# OpenBook.net
KiCad netlist of a schematic drawn in EAGLE
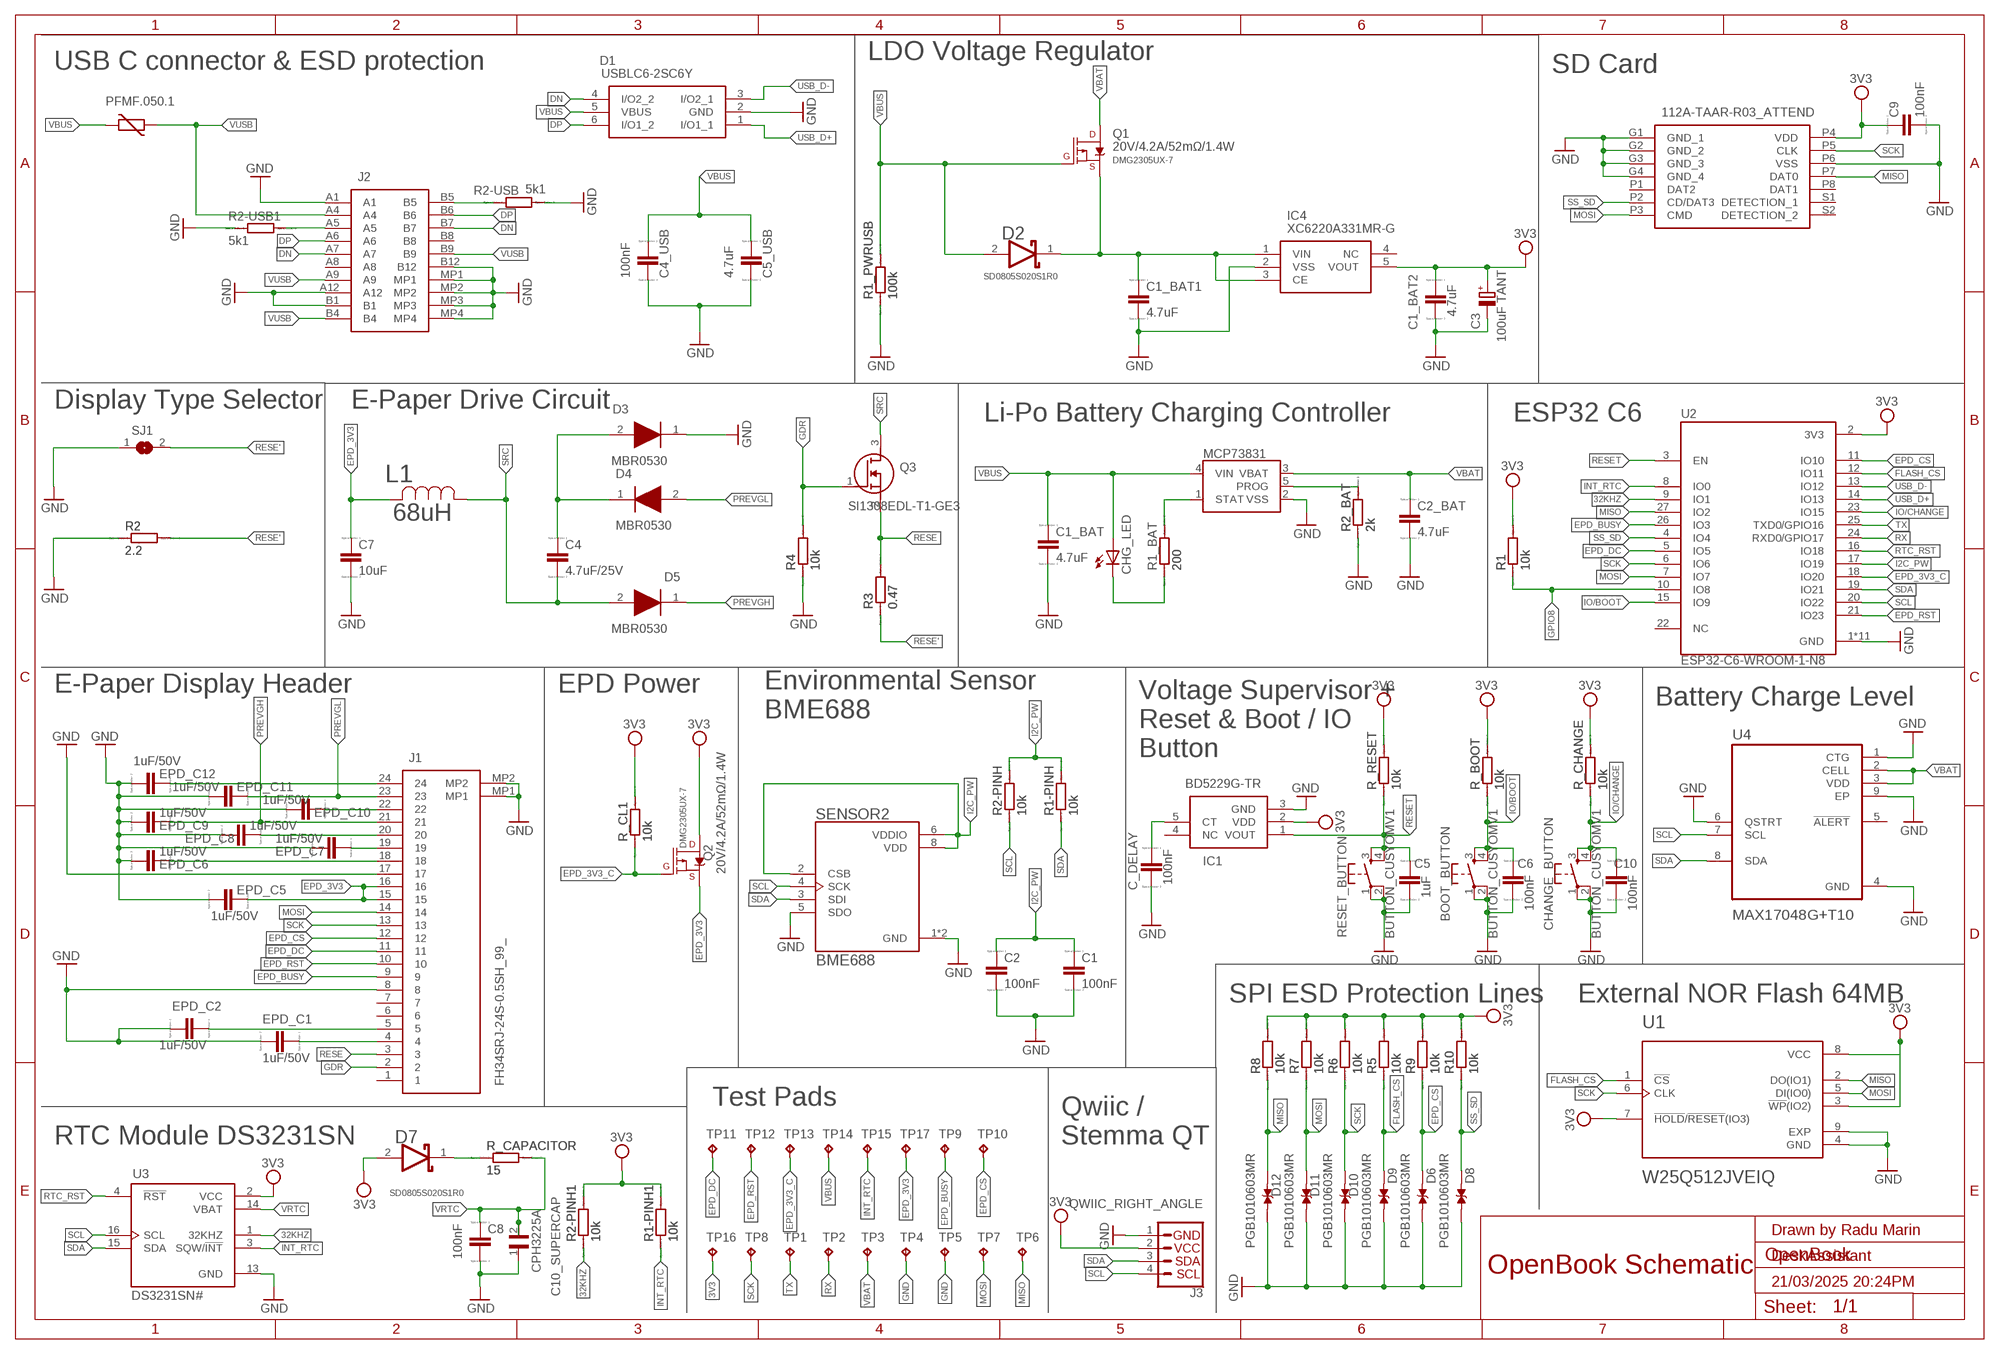
[diagram p0: schematic, sheet 1]

(export (version "E")
  (design (tool "Eeschema 10.0.6"))
  (components
    (comp (ref "BOOT_BUTTON")
      (value "BUTTON_CUSYOMV1")
      (footprint "eagle-import:MYBUTTON")
      (libsource (lib "eagle-import") (part "BUTTON_CUSYOMV1"))
    )
    (comp (ref "C1")
      (value "100nF")
      (footprint "eagle-import:EAGLE-LTSPICE_C0402")
      (libsource (lib "eagle-import") (part "EAGLE-LTSPICE_CC0402"))
    )
    (comp (ref "C1_BAT")
      (value "4.7uF")
      (footprint "eagle-import:EAGLE-LTSPICE_C0402")
      (libsource (lib "eagle-import") (part "EAGLE-LTSPICE_CC0402"))
    )
    (comp (ref "C1_BAT1")
      (value "4.7uF")
      (footprint "eagle-import:EAGLE-LTSPICE_C0402")
      (libsource (lib "eagle-import") (part "EAGLE-LTSPICE_CC0402"))
    )
    (comp (ref "C1_BAT2")
      (value "4.7uF")
      (footprint "eagle-import:EAGLE-LTSPICE_C0402")
      (libsource (lib "eagle-import") (part "EAGLE-LTSPICE_CC0402"))
    )
    (comp (ref "C2")
      (value "100nF")
      (footprint "eagle-import:EAGLE-LTSPICE_C0402")
      (libsource (lib "eagle-import") (part "EAGLE-LTSPICE_CC0402"))
    )
    (comp (ref "C2_BAT")
      (value "4.7uF")
      (footprint "eagle-import:EAGLE-LTSPICE_C0402")
      (libsource (lib "eagle-import") (part "EAGLE-LTSPICE_CC0402"))
    )
    (comp (ref "C3")
      (value "100uF TANT")
      (footprint "eagle-import:RCL_CT3528")
      (libsource (lib "eagle-import") (part "RCL_CPOL-EUCT3528"))
    )
    (comp (ref "C4")
      (value "4.7uF/25V")
      (footprint "eagle-import:EAGLE-LTSPICE_C0402")
      (libsource (lib "eagle-import") (part "EAGLE-LTSPICE_CC0402"))
    )
    (comp (ref "C4_USB")
      (value "100nF")
      (footprint "eagle-import:EAGLE-LTSPICE_C0402")
      (libsource (lib "eagle-import") (part "EAGLE-LTSPICE_CC0402"))
    )
    (comp (ref "C5")
      (value "1uF")
      (footprint "eagle-import:EAGLE-LTSPICE_C0402")
      (libsource (lib "eagle-import") (part "EAGLE-LTSPICE_CC0402"))
    )
    (comp (ref "C5_USB")
      (value "4.7uF")
      (footprint "eagle-import:EAGLE-LTSPICE_C0402")
      (libsource (lib "eagle-import") (part "EAGLE-LTSPICE_CC0402"))
    )
    (comp (ref "C6")
      (value "100nF")
      (footprint "eagle-import:EAGLE-LTSPICE_C0402")
      (libsource (lib "eagle-import") (part "EAGLE-LTSPICE_CC0402"))
    )
    (comp (ref "C7")
      (value "10uF")
      (footprint "eagle-import:EAGLE-LTSPICE_C0402")
      (libsource (lib "eagle-import") (part "EAGLE-LTSPICE_CC0402"))
    )
    (comp (ref "C8")
      (value "100nF")
      (footprint "eagle-import:EAGLE-LTSPICE_C0402")
      (libsource (lib "eagle-import") (part "EAGLE-LTSPICE_CC0402"))
    )
    (comp (ref "C9")
      (value "100nF")
      (footprint "eagle-import:EAGLE-LTSPICE_C0402")
      (libsource (lib "eagle-import") (part "EAGLE-LTSPICE_CC0402"))
    )
    (comp (ref "C10")
      (value "100nF")
      (footprint "eagle-import:EAGLE-LTSPICE_C0402")
      (libsource (lib "eagle-import") (part "EAGLE-LTSPICE_CC0402"))
    )
    (comp (ref "C10_SUPERCAP")
      (value "CPH3225A")
      (footprint "eagle-import:CAPCP3225X100N")
      (fields (field (name "MF") "Seiko Instruments"))
      (libsource (lib "eagle-import") (part "CPH3225A"))
    )
    (comp (ref "CHANGE_BUTTON")
      (value "BUTTON_CUSYOMV1")
      (footprint "eagle-import:MYBUTTON")
      (libsource (lib "eagle-import") (part "BUTTON_CUSYOMV1"))
    )
    (comp (ref "CHG_LED")
      (value "SMD-LED0603")
      (footprint "eagle-import:ADAFRUIT_CHIP-LED0603")
      (libsource (lib "eagle-import") (part "ADAFRUIT_LEDCHIP-LED0603"))
    )
    (comp (ref "C_DELAY")
      (value "100nF")
      (footprint "eagle-import:EAGLE-LTSPICE_C0402")
      (libsource (lib "eagle-import") (part "EAGLE-LTSPICE_CC0402"))
    )
    (comp (ref "D1")
      (value "USBLC6-2SC6Y")
      (footprint "eagle-import:SOT95P280X145-6N")
      (fields (field (name "MF") "STMicroelectronics"))
      (libsource (lib "eagle-import") (part "USBLC6-2SC6Y"))
    )
    (comp (ref "D2")
      (value "ESP32_WROVER_AVX---SD0805S020S1R0_AVX_SD0805S020S1R0_0_0AVX_SD0805S020S1R0_0_0")
      (footprint "eagle-import:ESP32_WROVER_AVX---SD0805S020S1R0_AVX_SD0805S020S1R0_0")
      (fields
        (field (name "DIGIKEY_PART_NUMBER") "478-7800-1-ND")
        (field (name "MF") "AVX")
        (field (name "MOUSER_PART_NUMBER") "581-SD0805S020S1R0")
      )
      (libsource (lib "eagle-import") (part "ESP32_WROVER_AVX---SD0805S020S1R0_AVX_SD0805S020S1R0_0_0AVX_SD0805S020S1R0_0_0"))
    )
    (comp (ref "D3")
      (value "MBR0530")
      (footprint "eagle-import:SOD3716X135N")
      (fields (field (name "MF") "ON Semiconductor"))
      (libsource (lib "eagle-import") (part "MBR0530"))
    )
    (comp (ref "D4")
      (value "MBR0530")
      (footprint "eagle-import:SOD3716X135N")
      (fields (field (name "MF") "ON Semiconductor"))
      (libsource (lib "eagle-import") (part "MBR0530"))
    )
    (comp (ref "D5")
      (value "MBR0530")
      (footprint "eagle-import:SOD3716X135N")
      (fields (field (name "MF") "ON Semiconductor"))
      (libsource (lib "eagle-import") (part "MBR0530"))
    )
    (comp (ref "D6")
      (value "PGB1010603MR")
      (footprint "eagle-import:DIOC1608X36N")
      (fields (field (name "MF") "Littelfuse Inc."))
      (libsource (lib "eagle-import") (part "PGB1010603MR"))
    )
    (comp (ref "D7")
      (value "ESP32_WROVER_AVX---SD0805S020S1R0_AVX_SD0805S020S1R0_0_0AVX_SD0805S020S1R0_0_0")
      (footprint "eagle-import:ESP32_WROVER_AVX---SD0805S020S1R0_AVX_SD0805S020S1R0_0")
      (fields
        (field (name "DIGIKEY_PART_NUMBER") "478-7800-1-ND")
        (field (name "MF") "AVX")
        (field (name "MOUSER_PART_NUMBER") "581-SD0805S020S1R0")
      )
      (libsource (lib "eagle-import") (part "ESP32_WROVER_AVX---SD0805S020S1R0_AVX_SD0805S020S1R0_0_0AVX_SD0805S020S1R0_0_0"))
    )
    (comp (ref "D8")
      (value "PGB1010603MR")
      (footprint "eagle-import:DIOC1608X36N")
      (fields (field (name "MF") "Littelfuse Inc."))
      (libsource (lib "eagle-import") (part "PGB1010603MR"))
    )
    (comp (ref "D9")
      (value "PGB1010603MR")
      (footprint "eagle-import:DIOC1608X36N")
      (fields (field (name "MF") "Littelfuse Inc."))
      (libsource (lib "eagle-import") (part "PGB1010603MR"))
    )
    (comp (ref "D10")
      (value "PGB1010603MR")
      (footprint "eagle-import:DIOC1608X36N")
      (fields (field (name "MF") "Littelfuse Inc."))
      (libsource (lib "eagle-import") (part "PGB1010603MR"))
    )
    (comp (ref "D11")
      (value "PGB1010603MR")
      (footprint "eagle-import:DIOC1608X36N")
      (fields (field (name "MF") "Littelfuse Inc."))
      (libsource (lib "eagle-import") (part "PGB1010603MR"))
    )
    (comp (ref "D12")
      (value "PGB1010603MR")
      (footprint "eagle-import:DIOC1608X36N")
      (fields (field (name "MF") "Littelfuse Inc."))
      (libsource (lib "eagle-import") (part "PGB1010603MR"))
    )
    (comp (ref "EPD_C1")
      (value "1uF/50V")
      (footprint "eagle-import:EAGLE-LTSPICE_C0402")
      (libsource (lib "eagle-import") (part "EAGLE-LTSPICE_CC0402"))
    )
    (comp (ref "EPD_C2")
      (value "1uF/50V")
      (footprint "eagle-import:EAGLE-LTSPICE_C0402")
      (libsource (lib "eagle-import") (part "EAGLE-LTSPICE_CC0402"))
    )
    (comp (ref "EPD_C5")
      (value "1uF/50V")
      (footprint "eagle-import:EAGLE-LTSPICE_C0402")
      (libsource (lib "eagle-import") (part "EAGLE-LTSPICE_CC0402"))
    )
    (comp (ref "EPD_C6")
      (value "1uF/50V")
      (footprint "eagle-import:EAGLE-LTSPICE_C0402")
      (libsource (lib "eagle-import") (part "EAGLE-LTSPICE_CC0402"))
    )
    (comp (ref "EPD_C7")
      (value "1uF/50V")
      (footprint "eagle-import:EAGLE-LTSPICE_C0402")
      (libsource (lib "eagle-import") (part "EAGLE-LTSPICE_CC0402"))
    )
    (comp (ref "EPD_C8")
      (value "1uF/50V")
      (footprint "eagle-import:EAGLE-LTSPICE_C0402")
      (libsource (lib "eagle-import") (part "EAGLE-LTSPICE_CC0402"))
    )
    (comp (ref "EPD_C9")
      (value "1uF/50V")
      (footprint "eagle-import:EAGLE-LTSPICE_C0402")
      (libsource (lib "eagle-import") (part "EAGLE-LTSPICE_CC0402"))
    )
    (comp (ref "EPD_C10")
      (value "1uF/50V")
      (footprint "eagle-import:EAGLE-LTSPICE_C0402")
      (libsource (lib "eagle-import") (part "EAGLE-LTSPICE_CC0402"))
    )
    (comp (ref "EPD_C11")
      (value "1uF/50V")
      (footprint "eagle-import:EAGLE-LTSPICE_C0402")
      (libsource (lib "eagle-import") (part "EAGLE-LTSPICE_CC0402"))
    )
    (comp (ref "EPD_C12")
      (value "1uF/50V")
      (footprint "eagle-import:EAGLE-LTSPICE_C0402")
      (libsource (lib "eagle-import") (part "EAGLE-LTSPICE_CC0402"))
    )
    (comp (ref "IC1")
      (value "BD5229G-TR")
      (footprint "eagle-import:SOT95P280X125-5N")
      (fields (field (name "MOUSER_PART_NUMBER") "755-BD5229G-TR"))
      (libsource (lib "eagle-import") (part "BD5229G-TR"))
    )
    (comp (ref "IC4")
      (value "XC6220A331MR-G")
      (footprint "eagle-import:SOT95P280X120-5N")
      (fields (field (name "MOUSER_PART_NUMBER") "865-XC6220A331MR-G"))
      (libsource (lib "eagle-import") (part "XC6220A331MR-G"))
    )
    (comp (ref "J1")
      (value "FH34SRJ-24S-0.5SH_99_")
      (footprint "eagle-import:FH34SRJ24S05SH99")
      (fields
        (field (name "MANUFACTURER_PART_NUMBER") "FH34SRJ-24S-0.5SH(99)")
        (field (name "MOUSER_PART_NUMBER") "798-FH34SRJ24S05SH99")
      )
      (libsource (lib "eagle-import") (part "FH34SRJ-24S-0.5SH_99_"))
    )
    (comp (ref "J2")
      (value "SAMACSYS_PARTS_USB4110-GF-A")
      (footprint "eagle-import:SAMACSYS_PARTS_USB4110GFA")
      (fields
        (field (name "MANUFACTURER_PART_NUMBER") "USB4110-GF-A")
        (field (name "MOUSER_PART_NUMBER") "640-USB4110-GF-A")
      )
      (libsource (lib "eagle-import") (part "SAMACSYS_PARTS_USB4110-GF-A"))
    )
    (comp (ref "J3")
      (value "QWIIC_RIGHT_ANGLE")
      (footprint "eagle-import:JST04_1MM_RA")
      (libsource (lib "eagle-import") (part "QWIIC_CONNECTORJS-1MM"))
    )
    (comp (ref "J10")
      (value "112A-TAAR-R03_ATTEND")
      (footprint "eagle-import:112ATAARR03ATTEND")
      (fields (field (name "MANUFACTURER_PART_NUMBER") "112A-TAAR-R03 ATTEND"))
      (libsource (lib "eagle-import") (part "112A-TAAR-R03_ATTEND"))
    )
    (comp (ref "L1")
      (value "68uH")
      (footprint "eagle-import:IND_4828-WE-TPC_WRE")
      (fields
        (field (name "MANUFACTURER_PART_NUMBER") "744043680")
        (field (name "COPYRIGHT") "Copyright (C) 2024 Ultra Librarian. All rights reserved.")
      )
      (libsource (lib "eagle-import") (part "744043680IND_4828-WE-TPC_WRE"))
    )
    (comp (ref "MCP73831")
      (value "ESP32_WROVER_SPARKFUN-IC-POWER_MCP73831")
      (footprint "eagle-import:ESP32_WROVER_SPARKFUN-IC-POWER_SOT23-5")
      (libsource (lib "eagle-import") (part "ESP32_WROVER_SPARKFUN-IC-POWER_MCP73831"))
    )
    (comp (ref "PFMF.050.1")
      (value "ESP32C6_VARISTORCN1812")
      (footprint "eagle-import:ESP32C6_VARISTOR_CT_CN1812")
      (libsource (lib "eagle-import") (part "ESP32C6_VARISTORCN1812"))
    )
    (comp (ref "Q1")
      (value "20V/4.2A/52mΩ/1.4W")
      (footprint "eagle-import:ESP32_WROVER_SPARKFUN-DISCRETESEMI_SOT23-3")
      (libsource (lib "eagle-import") (part "ESP32_WROVER_SPARKFUN-DISCRETESEMI_MOSFET_PCH-DMG2305UX-7"))
    )
    (comp (ref "Q2")
      (value "20V/4.2A/52mΩ/1.4W")
      (footprint "eagle-import:ESP32_WROVER_SPARKFUN-DISCRETESEMI_SOT23-3")
      (libsource (lib "eagle-import") (part "ESP32_WROVER_SPARKFUN-DISCRETESEMI_MOSFET_PCH-DMG2305UX-7"))
    )
    (comp (ref "Q3")
      (value "SI1308EDL-T1-GE3")
      (footprint "eagle-import:SOT65P210X110-3N")
      (fields (field (name "MF") "Vishay Siliconix"))
      (libsource (lib "eagle-import") (part "SI1308EDL-T1-GE3"))
    )
    (comp (ref "R1")
      (value "10k")
      (footprint "eagle-import:ESP32_WROVER_EAGLE-LTSPICE_R0402")
      (libsource (lib "eagle-import") (part "ESP32_WROVER_EAGLE-LTSPICE_RR0402"))
    )
    (comp (ref "R1-PINH")
      (value "10k")
      (footprint "eagle-import:ESP32_WROVER_EAGLE-LTSPICE_R0402")
      (libsource (lib "eagle-import") (part "ESP32_WROVER_EAGLE-LTSPICE_RR0402"))
    )
    (comp (ref "R1-PINH1")
      (value "10k")
      (footprint "eagle-import:ESP32_WROVER_EAGLE-LTSPICE_R0402")
      (libsource (lib "eagle-import") (part "ESP32_WROVER_EAGLE-LTSPICE_RR0402"))
    )
    (comp (ref "R1_BAT")
      (value "200")
      (footprint "eagle-import:ESP32_WROVER_EAGLE-LTSPICE_R0402")
      (libsource (lib "eagle-import") (part "ESP32_WROVER_EAGLE-LTSPICE_RR0402"))
    )
    (comp (ref "R1_PWRUSB")
      (value "100k")
      (footprint "eagle-import:ESP32_WROVER_EAGLE-LTSPICE_R0402")
      (libsource (lib "eagle-import") (part "ESP32_WROVER_EAGLE-LTSPICE_RR0402"))
    )
    (comp (ref "R2")
      (value "2.2")
      (footprint "eagle-import:ESP32_WROVER_EAGLE-LTSPICE_R0402")
      (libsource (lib "eagle-import") (part "ESP32_WROVER_EAGLE-LTSPICE_RR0402"))
    )
    (comp (ref "R2-PINH")
      (value "10k")
      (footprint "eagle-import:ESP32_WROVER_EAGLE-LTSPICE_R0402")
      (libsource (lib "eagle-import") (part "ESP32_WROVER_EAGLE-LTSPICE_RR0402"))
    )
    (comp (ref "R2-PINH1")
      (value "10k")
      (footprint "eagle-import:ESP32_WROVER_EAGLE-LTSPICE_R0402")
      (libsource (lib "eagle-import") (part "ESP32_WROVER_EAGLE-LTSPICE_RR0402"))
    )
    (comp (ref "R2-USB")
      (value "5k1")
      (footprint "eagle-import:ESP32_WROVER_EAGLE-LTSPICE_R0402")
      (libsource (lib "eagle-import") (part "ESP32_WROVER_EAGLE-LTSPICE_RR0402"))
    )
    (comp (ref "R2-USB1")
      (value "5k1")
      (footprint "eagle-import:ESP32_WROVER_EAGLE-LTSPICE_R0402")
      (libsource (lib "eagle-import") (part "ESP32_WROVER_EAGLE-LTSPICE_RR0402"))
    )
    (comp (ref "R2_BAT")
      (value "2k")
      (footprint "eagle-import:ESP32_WROVER_EAGLE-LTSPICE_R0402")
      (libsource (lib "eagle-import") (part "ESP32_WROVER_EAGLE-LTSPICE_RR0402"))
    )
    (comp (ref "R3")
      (value "0.47")
      (footprint "eagle-import:ESP32_WROVER_EAGLE-LTSPICE_R0402")
      (libsource (lib "eagle-import") (part "ESP32_WROVER_EAGLE-LTSPICE_RR0402"))
    )
    (comp (ref "R4")
      (value "10k")
      (footprint "eagle-import:ESP32_WROVER_EAGLE-LTSPICE_R0402")
      (libsource (lib "eagle-import") (part "ESP32_WROVER_EAGLE-LTSPICE_RR0402"))
    )
    (comp (ref "R5")
      (value "10k")
      (footprint "eagle-import:ESP32_WROVER_EAGLE-LTSPICE_R0402")
      (libsource (lib "eagle-import") (part "ESP32_WROVER_EAGLE-LTSPICE_RR0402"))
    )
    (comp (ref "R6")
      (value "10k")
      (footprint "eagle-import:ESP32_WROVER_EAGLE-LTSPICE_R0402")
      (libsource (lib "eagle-import") (part "ESP32_WROVER_EAGLE-LTSPICE_RR0402"))
    )
    (comp (ref "R7")
      (value "10k")
      (footprint "eagle-import:ESP32_WROVER_EAGLE-LTSPICE_R0402")
      (libsource (lib "eagle-import") (part "ESP32_WROVER_EAGLE-LTSPICE_RR0402"))
    )
    (comp (ref "R8")
      (value "10k")
      (footprint "eagle-import:ESP32_WROVER_EAGLE-LTSPICE_R0402")
      (libsource (lib "eagle-import") (part "ESP32_WROVER_EAGLE-LTSPICE_RR0402"))
    )
    (comp (ref "R9")
      (value "10k")
      (footprint "eagle-import:ESP32_WROVER_EAGLE-LTSPICE_R0402")
      (libsource (lib "eagle-import") (part "ESP32_WROVER_EAGLE-LTSPICE_RR0402"))
    )
    (comp (ref "R10")
      (value "10k")
      (footprint "eagle-import:ESP32_WROVER_EAGLE-LTSPICE_R0402")
      (libsource (lib "eagle-import") (part "ESP32_WROVER_EAGLE-LTSPICE_RR0402"))
    )
    (comp (ref "RESET_BUTTON")
      (value "BUTTON_CUSYOMV1")
      (footprint "eagle-import:MYBUTTON")
      (libsource (lib "eagle-import") (part "BUTTON_CUSYOMV1"))
    )
    (comp (ref "R_BOOT")
      (value "10k")
      (footprint "eagle-import:ESP32_WROVER_EAGLE-LTSPICE_R0402")
      (libsource (lib "eagle-import") (part "ESP32_WROVER_EAGLE-LTSPICE_RR0402"))
    )
    (comp (ref "R_CAPACITOR")
      (value "15")
      (footprint "eagle-import:ESP32_WROVER_EAGLE-LTSPICE_R0402")
      (libsource (lib "eagle-import") (part "ESP32_WROVER_EAGLE-LTSPICE_RR0402"))
    )
    (comp (ref "R_CHANGE")
      (value "10k")
      (footprint "eagle-import:ESP32_WROVER_EAGLE-LTSPICE_R0402")
      (libsource (lib "eagle-import") (part "ESP32_WROVER_EAGLE-LTSPICE_RR0402"))
    )
    (comp (ref "R_CL1")
      (value "10k")
      (footprint "eagle-import:ESP32_WROVER_EAGLE-LTSPICE_R0402")
      (libsource (lib "eagle-import") (part "ESP32_WROVER_EAGLE-LTSPICE_RR0402"))
    )
    (comp (ref "R_RESET")
      (value "10k")
      (footprint "eagle-import:ESP32_WROVER_EAGLE-LTSPICE_R0402")
      (libsource (lib "eagle-import") (part "ESP32_WROVER_EAGLE-LTSPICE_RR0402"))
    )
    (comp (ref "SENSOR2")
      (value "BME688")
      (footprint "eagle-import:ESP32_WROVER_BME680_PSON80P300X300X100-8N")
      (fields (field (name "MF") "Bosch Sensortec") (field (name "MP") "BME680"))
      (libsource (lib "eagle-import") (part "ESP32_WROVER_BME680_BME680"))
    )
    (comp (ref "SJ1") (value "1m") (footprint "eagle-import:SJ") (libsource (lib "eagle-import") (part "SJ")))
    (comp (ref "TP1")
      (value "TPTP20R")
      (footprint "eagle-import:TP20R")
      (libsource (lib "eagle-import") (part "TPTP20R"))
    )
    (comp (ref "TP2")
      (value "TPTP20R")
      (footprint "eagle-import:TP20R")
      (libsource (lib "eagle-import") (part "TPTP20R"))
    )
    (comp (ref "TP3")
      (value "TPTP20R")
      (footprint "eagle-import:TP20R")
      (libsource (lib "eagle-import") (part "TPTP20R"))
    )
    (comp (ref "TP4")
      (value "TPTP20R")
      (footprint "eagle-import:TP20R")
      (libsource (lib "eagle-import") (part "TPTP20R"))
    )
    (comp (ref "TP5")
      (value "TPTP20R")
      (footprint "eagle-import:TP20R")
      (libsource (lib "eagle-import") (part "TPTP20R"))
    )
    (comp (ref "TP6")
      (value "TPTP20R")
      (footprint "eagle-import:TP20R")
      (libsource (lib "eagle-import") (part "TPTP20R"))
    )
    (comp (ref "TP7")
      (value "TPTP20R")
      (footprint "eagle-import:TP20R")
      (libsource (lib "eagle-import") (part "TPTP20R"))
    )
    (comp (ref "TP8")
      (value "TPTP20R")
      (footprint "eagle-import:TP20R")
      (libsource (lib "eagle-import") (part "TPTP20R"))
    )
    (comp (ref "TP9")
      (value "TPTP20R")
      (footprint "eagle-import:TP20R")
      (libsource (lib "eagle-import") (part "TPTP20R"))
    )
    (comp (ref "TP10")
      (value "TPTP20R")
      (footprint "eagle-import:TP20R")
      (libsource (lib "eagle-import") (part "TPTP20R"))
    )
    (comp (ref "TP11")
      (value "TPTP20R")
      (footprint "eagle-import:TP20R")
      (libsource (lib "eagle-import") (part "TPTP20R"))
    )
    (comp (ref "TP12")
      (value "TPTP20R")
      (footprint "eagle-import:TP20R")
      (libsource (lib "eagle-import") (part "TPTP20R"))
    )
    (comp (ref "TP13")
      (value "TPTP20R")
      (footprint "eagle-import:TP20R")
      (libsource (lib "eagle-import") (part "TPTP20R"))
    )
    (comp (ref "TP14")
      (value "TPTP20R")
      (footprint "eagle-import:TP20R")
      (libsource (lib "eagle-import") (part "TPTP20R"))
    )
    (comp (ref "TP15")
      (value "TPTP20R")
      (footprint "eagle-import:TP20R")
      (libsource (lib "eagle-import") (part "TPTP20R"))
    )
    (comp (ref "TP16")
      (value "TPTP20R")
      (footprint "eagle-import:TP20R")
      (libsource (lib "eagle-import") (part "TPTP20R"))
    )
    (comp (ref "TP17")
      (value "TPTP20R")
      (footprint "eagle-import:TP20R")
      (libsource (lib "eagle-import") (part "TPTP20R"))
    )
    (comp (ref "U1")
      (value "W25Q512JVEIQ")
      (footprint "eagle-import:SON127P600X800X80-9N")
      (fields (field (name "MF") "Winbond Electronics"))
      (libsource (lib "eagle-import") (part "W25Q512JVEIQ"))
    )
    (comp (ref "U2")
      (value "ESP32-C6-WROOM-1-N8")
      (footprint "eagle-import:XCVR_ESP32-C6-WROOM-1-N8")
      (fields (field (name "MF") "Espressif Systems"))
      (libsource (lib "eagle-import") (part "ESP32-C6-WROOM-1-N8"))
    )
    (comp (ref "U3")
      (value "DS3231SN#")
      (footprint "eagle-import:SOIC127P1032X265-16N")
      (fields (field (name "MF") "Analog Devices"))
      (libsource (lib "eagle-import") (part "DS3231SN#"))
    )
    (comp (ref "U4")
      (value "MAX17048G+T10")
      (footprint "eagle-import:SON50P200X200X80-9N")
      (fields (field (name "MF") "Analog Devices"))
      (libsource (lib "eagle-import") (part "MAX17048G+T10"))
    )
  )
  (nets
    (net (code "1") (name "3V3") (class "Default")
      (node (ref "C1_BAT2") (pin "1") (pinfunction "1_1") (pintype "passive"))
      (node (ref "C3") (pin "+") (pinfunction "+_+") (pintype "passive"))
      (node (ref "C9") (pin "1") (pinfunction "1_1") (pintype "passive"))
      (node (ref "D7") (pin "2") (pinfunction "ANODE_2") (pintype "bidirectional"))
      (node (ref "IC1") (pin "2") (pinfunction "VDD_2") (pintype "bidirectional"))
      (node (ref "IC4") (pin "5") (pinfunction "VOUT_5") (pintype "bidirectional"))
      (node (ref "J10") (pin "P4") (pinfunction "VDD_P4") (pintype "bidirectional"))
      (node (ref "J3") (pin "2") (pinfunction "2_2") (pintype "power_in"))
      (node (ref "Q2") (pin "3") (pinfunction "D_3") (pintype "bidirectional"))
      (node (ref "R1") (pin "2") (pinfunction "2_2") (pintype "passive"))
      (node (ref "R1-PINH1") (pin "2") (pinfunction "2_2") (pintype "passive"))
      (node (ref "R10") (pin "2") (pinfunction "2_2") (pintype "passive"))
      (node (ref "R2-PINH1") (pin "2") (pinfunction "2_2") (pintype "passive"))
      (node (ref "R5") (pin "2") (pinfunction "2_2") (pintype "passive"))
      (node (ref "R6") (pin "2") (pinfunction "2_2") (pintype "passive"))
      (node (ref "R7") (pin "2") (pinfunction "2_2") (pintype "passive"))
      (node (ref "R8") (pin "2") (pinfunction "2_2") (pintype "passive"))
      (node (ref "R9") (pin "2") (pinfunction "2_2") (pintype "passive"))
      (node (ref "R_BOOT") (pin "2") (pinfunction "2_2") (pintype "passive"))
      (node (ref "R_CHANGE") (pin "2") (pinfunction "2_2") (pintype "passive"))
      (node (ref "R_CL1") (pin "2") (pinfunction "2_2") (pintype "passive"))
      (node (ref "R_RESET") (pin "2") (pinfunction "2_2") (pintype "passive"))
      (node (ref "TP16") (pin "TP") (pinfunction "TP_TP") (pintype "input"))
      (node (ref "U1") (pin "3") (pinfunction "~{WP}(IO2)_3") (pintype "bidirectional"))
      (node (ref "U1") (pin "7") (pinfunction "~{HOLD}/~{RESET}(IO3)_7") (pintype "bidirectional"))
      (node (ref "U1") (pin "8") (pinfunction "VCC_8") (pintype "power_in"))
      (node (ref "U2") (pin "2") (pinfunction "3V3_2") (pintype "power_in"))
      (node (ref "U3") (pin "2") (pinfunction "VCC_2") (pintype "power_in"))
    )
    (net (code "2") (name "32KHZ") (class "Default")
      (node (ref "R2-PINH1") (pin "1") (pinfunction "1_1") (pintype "passive"))
      (node (ref "U2") (pin "9") (pinfunction "IO1_9") (pintype "bidirectional"))
      (node (ref "U3") (pin "1") (pinfunction "32KHZ_1") (pintype "output"))
    )
    (net (code "3") (name "DN") (class "Default")
      (node (ref "D1") (pin "4") (pinfunction "I/O2_2_4") (pintype "bidirectional"))
      (node (ref "J2") (pin "A7") (pinfunction "A7_A7") (pintype "bidirectional"))
      (node (ref "J2") (pin "B7") (pinfunction "B7_B7") (pintype "bidirectional"))
    )
    (net (code "4") (name "DP") (class "Default")
      (node (ref "D1") (pin "6") (pinfunction "I/O1_2_6") (pintype "bidirectional"))
      (node (ref "J2") (pin "A6") (pinfunction "A6_A6") (pintype "bidirectional"))
      (node (ref "J2") (pin "B6") (pinfunction "B6_B6") (pintype "bidirectional"))
    )
    (net (code "5") (name "EPD_3V3") (class "Default")
      (node (ref "C7") (pin "1") (pinfunction "1_1") (pintype "passive"))
      (node (ref "EPD_C5") (pin "1") (pinfunction "1_1") (pintype "passive"))
      (node (ref "J1") (pin "15") (pinfunction "15_15") (pintype "bidirectional"))
      (node (ref "J1") (pin "16") (pinfunction "16_16") (pintype "bidirectional"))
      (node (ref "L1") (pin "2") (pinfunction "2_2") (pintype "passive"))
      (node (ref "Q2") (pin "2") (pinfunction "S_2") (pintype "bidirectional"))
      (node (ref "TP17") (pin "TP") (pinfunction "TP_TP") (pintype "input"))
    )
    (net (code "6") (name "EPD_3V3_C") (class "Default")
      (node (ref "Q2") (pin "1") (pinfunction "G_1") (pintype "bidirectional"))
      (node (ref "R_CL1") (pin "1") (pinfunction "1_1") (pintype "passive"))
      (node (ref "TP13") (pin "TP") (pinfunction "TP_TP") (pintype "input"))
      (node (ref "U2") (pin "18") (pinfunction "IO20_18") (pintype "bidirectional"))
    )
    (net (code "7") (name "EPD_BUSY") (class "Default")
      (node (ref "J1") (pin "9") (pinfunction "9_9") (pintype "bidirectional"))
      (node (ref "TP9") (pin "TP") (pinfunction "TP_TP") (pintype "input"))
      (node (ref "U2") (pin "26") (pinfunction "IO3_26") (pintype "bidirectional"))
    )
    (net (code "8") (name "EPD_CS") (class "Default")
      (node (ref "D6") (pin "2") (pinfunction "2_2") (pintype "passive"))
      (node (ref "J1") (pin "12") (pinfunction "12_12") (pintype "bidirectional"))
      (node (ref "R9") (pin "1") (pinfunction "1_1") (pintype "passive"))
      (node (ref "TP10") (pin "TP") (pinfunction "TP_TP") (pintype "input"))
      (node (ref "U2") (pin "11") (pinfunction "IO10_11") (pintype "bidirectional"))
    )
    (net (code "9") (name "EPD_DC") (class "Default")
      (node (ref "J1") (pin "11") (pinfunction "11_11") (pintype "bidirectional"))
      (node (ref "TP11") (pin "TP") (pinfunction "TP_TP") (pintype "input"))
      (node (ref "U2") (pin "5") (pinfunction "IO5_5") (pintype "bidirectional"))
    )
    (net (code "10") (name "EPD_RST") (class "Default")
      (node (ref "J1") (pin "10") (pinfunction "10_10") (pintype "bidirectional"))
      (node (ref "TP12") (pin "TP") (pinfunction "TP_TP") (pintype "input"))
      (node (ref "U2") (pin "21") (pinfunction "IO23_21") (pintype "bidirectional"))
    )
    (net (code "11") (name "FLASH_CS") (class "Default")
      (node (ref "D9") (pin "2") (pinfunction "2_2") (pintype "passive"))
      (node (ref "R5") (pin "1") (pinfunction "1_1") (pintype "passive"))
      (node (ref "U1") (pin "1") (pinfunction "~{CS}_1") (pintype "input"))
      (node (ref "U2") (pin "12") (pinfunction "IO11_12") (pintype "bidirectional"))
    )
    (net (code "12") (name "GDR") (class "Default")
      (node (ref "J1") (pin "2") (pinfunction "2_2") (pintype "bidirectional"))
      (node (ref "Q3") (pin "1") (pinfunction "G_1") (pintype "bidirectional"))
      (node (ref "R4") (pin "2") (pinfunction "2_2") (pintype "passive"))
    )
    (net (code "13") (name "GND") (class "Default")
      (node (ref "BOOT_BUTTON") (pin "1") (pinfunction "1_1") (pintype "passive"))
      (node (ref "BOOT_BUTTON") (pin "2") (pinfunction "2_2") (pintype "passive"))
      (node (ref "C1") (pin "2") (pinfunction "2_2") (pintype "passive"))
      (node (ref "C10") (pin "2") (pinfunction "2_2") (pintype "passive"))
      (node (ref "C10_SUPERCAP") (pin "1") (pinfunction "1_1") (pintype "passive"))
      (node (ref "C1_BAT") (pin "2") (pinfunction "2_2") (pintype "passive"))
      (node (ref "C1_BAT1") (pin "2") (pinfunction "2_2") (pintype "passive"))
      (node (ref "C1_BAT2") (pin "2") (pinfunction "2_2") (pintype "passive"))
      (node (ref "C2") (pin "2") (pinfunction "2_2") (pintype "passive"))
      (node (ref "C2_BAT") (pin "2") (pinfunction "2_2") (pintype "passive"))
      (node (ref "C3") (pin "-") (pinfunction "-_-") (pintype "passive"))
      (node (ref "C4_USB") (pin "2") (pinfunction "2_2") (pintype "passive"))
      (node (ref "C5") (pin "2") (pinfunction "2_2") (pintype "passive"))
      (node (ref "C5_USB") (pin "2") (pinfunction "2_2") (pintype "passive"))
      (node (ref "C6") (pin "2") (pinfunction "2_2") (pintype "passive"))
      (node (ref "C7") (pin "2") (pinfunction "2_2") (pintype "passive"))
      (node (ref "C8") (pin "2") (pinfunction "2_2") (pintype "passive"))
      (node (ref "C9") (pin "2") (pinfunction "2_2") (pintype "passive"))
      (node (ref "CHANGE_BUTTON") (pin "1") (pinfunction "1_1") (pintype "passive"))
      (node (ref "CHANGE_BUTTON") (pin "2") (pinfunction "2_2") (pintype "passive"))
      (node (ref "C_DELAY") (pin "2") (pinfunction "2_2") (pintype "passive"))
      (node (ref "D1") (pin "2") (pinfunction "GND_2") (pintype "bidirectional"))
      (node (ref "D10") (pin "1") (pinfunction "1_1") (pintype "passive"))
      (node (ref "D11") (pin "1") (pinfunction "1_1") (pintype "passive"))
      (node (ref "D12") (pin "1") (pinfunction "1_1") (pintype "passive"))
      (node (ref "D3") (pin "1") (pinfunction "K_1") (pintype "bidirectional"))
      (node (ref "D6") (pin "1") (pinfunction "1_1") (pintype "passive"))
      (node (ref "D8") (pin "1") (pinfunction "1_1") (pintype "passive"))
      (node (ref "D9") (pin "1") (pinfunction "1_1") (pintype "passive"))
      (node (ref "EPD_C1") (pin "2") (pinfunction "2_2") (pintype "passive"))
      (node (ref "EPD_C10") (pin "2") (pinfunction "2_2") (pintype "passive"))
      (node (ref "EPD_C11") (pin "2") (pinfunction "2_2") (pintype "passive"))
      (node (ref "EPD_C12") (pin "2") (pinfunction "2_2") (pintype "passive"))
      (node (ref "EPD_C2") (pin "2") (pinfunction "2_2") (pintype "passive"))
      (node (ref "EPD_C5") (pin "2") (pinfunction "2_2") (pintype "passive"))
      (node (ref "EPD_C6") (pin "2") (pinfunction "2_2") (pintype "passive"))
      (node (ref "EPD_C7") (pin "2") (pinfunction "2_2") (pintype "passive"))
      (node (ref "EPD_C8") (pin "2") (pinfunction "2_2") (pintype "passive"))
      (node (ref "EPD_C9") (pin "2") (pinfunction "2_2") (pintype "passive"))
      (node (ref "IC1") (pin "3") (pinfunction "GND_3") (pintype "bidirectional"))
      (node (ref "IC4") (pin "2") (pinfunction "VSS_2") (pintype "bidirectional"))
      (node (ref "J1") (pin "17") (pinfunction "17_17") (pintype "bidirectional"))
      (node (ref "J1") (pin "8") (pinfunction "8_8") (pintype "bidirectional"))
      (node (ref "J1") (pin "MP1") (pinfunction "MP1_MP1") (pintype "bidirectional"))
      (node (ref "J1") (pin "MP2") (pinfunction "MP2_MP2") (pintype "bidirectional"))
      (node (ref "J10") (pin "G1") (pinfunction "GND_1_G1") (pintype "bidirectional"))
      (node (ref "J10") (pin "G2") (pinfunction "GND_2_G2") (pintype "bidirectional"))
      (node (ref "J10") (pin "G3") (pinfunction "GND_3_G3") (pintype "bidirectional"))
      (node (ref "J10") (pin "G4") (pinfunction "GND_4_G4") (pintype "bidirectional"))
      (node (ref "J10") (pin "P6") (pinfunction "VSS_P6") (pintype "bidirectional"))
      (node (ref "J2") (pin "A1") (pinfunction "A1_A1") (pintype "bidirectional"))
      (node (ref "J2") (pin "A12") (pinfunction "A12_A12") (pintype "bidirectional"))
      (node (ref "J2") (pin "B1") (pinfunction "B1_B1") (pintype "bidirectional"))
      (node (ref "J2") (pin "B12") (pinfunction "B12_B12") (pintype "bidirectional"))
      (node (ref "J2") (pin "MP1") (pinfunction "MP1_MP1") (pintype "bidirectional"))
      (node (ref "J2") (pin "MP2") (pinfunction "MP2_MP2") (pintype "bidirectional"))
      (node (ref "J2") (pin "MP3") (pinfunction "MP3_MP3") (pintype "bidirectional"))
      (node (ref "J2") (pin "MP4") (pinfunction "MP4_MP4") (pintype "bidirectional"))
      (node (ref "J3") (pin "1") (pinfunction "1_1") (pintype "power_in"))
      (node (ref "MCP73831") (pin "2") (pinfunction "VSS_2") (pintype "power_in"))
      (node (ref "R1_PWRUSB") (pin "1") (pinfunction "1_1") (pintype "passive"))
      (node (ref "R2") (pin "1") (pinfunction "1_1") (pintype "passive"))
      (node (ref "R2-USB") (pin "2") (pinfunction "2_2") (pintype "passive"))
      (node (ref "R2-USB1") (pin "1") (pinfunction "1_1") (pintype "passive"))
      (node (ref "R2_BAT") (pin "1") (pinfunction "1_1") (pintype "passive"))
      (node (ref "R4") (pin "1") (pinfunction "1_1") (pintype "passive"))
      (node (ref "RESET_BUTTON") (pin "1") (pinfunction "1_1") (pintype "passive"))
      (node (ref "RESET_BUTTON") (pin "2") (pinfunction "2_2") (pintype "passive"))
      (node (ref "SENSOR2") (pin "1") (pinfunction "GND_1") (pintype "power_in"))
      (node (ref "SENSOR2") (pin "5") (pinfunction "SDO_5") (pintype "bidirectional"))
      (node (ref "SENSOR2") (pin "7") (pinfunction "GND_7") (pintype "power_in"))
      (node (ref "SJ1") (pin "1") (pinfunction "1_1") (pintype "passive"))
      (node (ref "TP4") (pin "TP") (pinfunction "TP_TP") (pintype "input"))
      (node (ref "TP5") (pin "TP") (pinfunction "TP_TP") (pintype "input"))
      (node (ref "U1") (pin "4") (pinfunction "GND_4") (pintype "power_in"))
      (node (ref "U1") (pin "9") (pinfunction "EXP_9") (pintype "passive"))
      (node (ref "U2") (pin "1") (pinfunction "GND_1") (pintype "power_in"))
      (node (ref "U2") (pin "28") (pinfunction "GND_28") (pintype "power_in"))
      (node (ref "U2") (pin "29_1") (pinfunction "GND_29_1") (pintype "power_in"))
      (node (ref "U2") (pin "29_2") (pinfunction "GND_29_2") (pintype "power_in"))
      (node (ref "U2") (pin "29_3") (pinfunction "GND_29_3") (pintype "power_in"))
      (node (ref "U2") (pin "29_4") (pinfunction "GND_29_4") (pintype "power_in"))
      (node (ref "U2") (pin "29_5") (pinfunction "GND_29_5") (pintype "power_in"))
      (node (ref "U2") (pin "29_6") (pinfunction "GND_29_6") (pintype "power_in"))
      (node (ref "U2") (pin "29_7") (pinfunction "GND_29_7") (pintype "power_in"))
      (node (ref "U2") (pin "29_8") (pinfunction "GND_29_8") (pintype "power_in"))
      (node (ref "U2") (pin "29_9") (pinfunction "GND_29_9") (pintype "power_in"))
      (node (ref "U3") (pin "13") (pinfunction "GND_13") (pintype "power_in"))
      (node (ref "U4") (pin "1") (pinfunction "CTG_1") (pintype "power_in"))
      (node (ref "U4") (pin "4") (pinfunction "GND_4") (pintype "power_in"))
      (node (ref "U4") (pin "6") (pinfunction "QSTRT_6") (pintype "input"))
      (node (ref "U4") (pin "9") (pinfunction "EP_9") (pintype "power_in"))
    )
    (net (code "14") (name "GPIO8") (class "Default")
      (node (ref "R1") (pin "1") (pinfunction "1_1") (pintype "passive"))
      (node (ref "U2") (pin "10") (pinfunction "IO8_10") (pintype "bidirectional"))
    )
    (net (code "15") (name "I2C_PW") (class "Default")
      (node (ref "C1") (pin "1") (pinfunction "1_1") (pintype "passive"))
      (node (ref "C2") (pin "1") (pinfunction "1_1") (pintype "passive"))
      (node (ref "R1-PINH") (pin "2") (pinfunction "2_2") (pintype "passive"))
      (node (ref "R2-PINH") (pin "2") (pinfunction "2_2") (pintype "passive"))
      (node (ref "SENSOR2") (pin "2") (pinfunction "CSB_2") (pintype "input"))
      (node (ref "SENSOR2") (pin "6") (pinfunction "VDDIO_6") (pintype "power_in"))
      (node (ref "SENSOR2") (pin "8") (pinfunction "VDD_8") (pintype "power_in"))
      (node (ref "U2") (pin "17") (pinfunction "IO19_17") (pintype "bidirectional"))
    )
    (net (code "16") (name "INT_RTC") (class "Default")
      (node (ref "R1-PINH1") (pin "1") (pinfunction "1_1") (pintype "passive"))
      (node (ref "TP15") (pin "TP") (pinfunction "TP_TP") (pintype "input"))
      (node (ref "U2") (pin "8") (pinfunction "IO0_8") (pintype "bidirectional"))
      (node (ref "U3") (pin "3") (pinfunction "SQW/~{INT}_3") (pintype "output"))
    )
    (net (code "17") (name "IO{slash}BOOT") (class "Default")
      (node (ref "BOOT_BUTTON") (pin "3") (pinfunction "3_3") (pintype "passive"))
      (node (ref "BOOT_BUTTON") (pin "4") (pinfunction "4_4") (pintype "passive"))
      (node (ref "C6") (pin "1") (pinfunction "1_1") (pintype "passive"))
      (node (ref "R_BOOT") (pin "1") (pinfunction "1_1") (pintype "passive"))
      (node (ref "U2") (pin "15") (pinfunction "IO9_15") (pintype "bidirectional"))
    )
    (net (code "18") (name "IO{slash}CHANGE") (class "Default")
      (node (ref "C10") (pin "1") (pinfunction "1_1") (pintype "passive"))
      (node (ref "CHANGE_BUTTON") (pin "3") (pinfunction "3_3") (pintype "passive"))
      (node (ref "CHANGE_BUTTON") (pin "4") (pinfunction "4_4") (pintype "passive"))
      (node (ref "R_CHANGE") (pin "1") (pinfunction "1_1") (pintype "passive"))
      (node (ref "U2") (pin "23") (pinfunction "IO15_23") (pintype "bidirectional"))
    )
    (net (code "19") (name "MISO") (class "Default")
      (node (ref "D12") (pin "2") (pinfunction "2_2") (pintype "passive"))
      (node (ref "J10") (pin "P7") (pinfunction "DAT0_P7") (pintype "bidirectional"))
      (node (ref "R8") (pin "1") (pinfunction "1_1") (pintype "passive"))
      (node (ref "TP6") (pin "TP") (pinfunction "TP_TP") (pintype "input"))
      (node (ref "U1") (pin "2") (pinfunction "DO(IO1)_2") (pintype "bidirectional"))
      (node (ref "U2") (pin "27") (pinfunction "IO2_27") (pintype "bidirectional"))
    )
    (net (code "20") (name "MOSI") (class "Default")
      (node (ref "D11") (pin "2") (pinfunction "2_2") (pintype "passive"))
      (node (ref "J1") (pin "14") (pinfunction "14_14") (pintype "bidirectional"))
      (node (ref "J10") (pin "P3") (pinfunction "CMD_P3") (pintype "bidirectional"))
      (node (ref "R7") (pin "1") (pinfunction "1_1") (pintype "passive"))
      (node (ref "TP7") (pin "TP") (pinfunction "TP_TP") (pintype "input"))
      (node (ref "U1") (pin "5") (pinfunction "DI(IO0)_5") (pintype "bidirectional"))
      (node (ref "U2") (pin "7") (pinfunction "IO7_7") (pintype "bidirectional"))
    )
    (net (code "21") (name "Net-(CHG_LED-PadC)") (class "Default")
      (node (ref "CHG_LED") (pin "C") (pinfunction "C_C") (pintype "passive"))
      (node (ref "R1_BAT") (pin "1") (pinfunction "1_1") (pintype "passive"))
    )
    (net (code "22") (name "Net-(D2-CATHODE)") (class "Default")
      (node (ref "C1_BAT1") (pin "1") (pinfunction "1_1") (pintype "passive"))
      (node (ref "D2") (pin "1") (pinfunction "CATHODE_1") (pintype "bidirectional"))
      (node (ref "IC4") (pin "1") (pinfunction "VIN_1") (pintype "bidirectional"))
      (node (ref "IC4") (pin "3") (pinfunction "CE_3") (pintype "bidirectional"))
      (node (ref "Q1") (pin "2") (pinfunction "S_2") (pintype "bidirectional"))
    )
    (net (code "23") (name "Net-(D3-A)") (class "Default")
      (node (ref "C4") (pin "1") (pinfunction "1_1") (pintype "passive"))
      (node (ref "D3") (pin "2") (pinfunction "A_2") (pintype "bidirectional"))
      (node (ref "D4") (pin "1") (pinfunction "K_1") (pintype "bidirectional"))
    )
    (net (code "24") (name "Net-(D7-CATHODE)") (class "Default")
      (node (ref "D7") (pin "1") (pinfunction "CATHODE_1") (pintype "bidirectional"))
      (node (ref "R_CAPACITOR") (pin "1") (pinfunction "1_1") (pintype "passive"))
    )
    (net (code "25") (name "Net-(EPD_C1-Pad1)") (class "Default")
      (node (ref "EPD_C1") (pin "1") (pinfunction "1_1") (pintype "passive"))
      (node (ref "J1") (pin "4") (pinfunction "4_4") (pintype "bidirectional"))
    )
    (net (code "26") (name "Net-(EPD_C2-Pad1)") (class "Default")
      (node (ref "EPD_C2") (pin "1") (pinfunction "1_1") (pintype "passive"))
      (node (ref "J1") (pin "5") (pinfunction "5_5") (pintype "bidirectional"))
    )
    (net (code "27") (name "Net-(EPD_C6-Pad1)") (class "Default")
      (node (ref "EPD_C6") (pin "1") (pinfunction "1_1") (pintype "passive"))
      (node (ref "J1") (pin "18") (pinfunction "18_18") (pintype "bidirectional"))
    )
    (net (code "28") (name "Net-(EPD_C7-Pad1)") (class "Default")
      (node (ref "EPD_C7") (pin "1") (pinfunction "1_1") (pintype "passive"))
      (node (ref "J1") (pin "19") (pinfunction "19_19") (pintype "bidirectional"))
    )
    (net (code "29") (name "Net-(EPD_C8-Pad1)") (class "Default")
      (node (ref "EPD_C8") (pin "1") (pinfunction "1_1") (pintype "passive"))
      (node (ref "J1") (pin "20") (pinfunction "20_20") (pintype "bidirectional"))
    )
    (net (code "30") (name "Net-(EPD_C10-Pad1)") (class "Default")
      (node (ref "EPD_C10") (pin "1") (pinfunction "1_1") (pintype "passive"))
      (node (ref "J1") (pin "22") (pinfunction "22_22") (pintype "bidirectional"))
    )
    (net (code "31") (name "Net-(EPD_C12-Pad1)") (class "Default")
      (node (ref "EPD_C12") (pin "1") (pinfunction "1_1") (pintype "passive"))
      (node (ref "J1") (pin "24") (pinfunction "24_24") (pintype "bidirectional"))
    )
    (net (code "32") (name "Net-(IC1-CT)") (class "Default")
      (node (ref "C_DELAY") (pin "1") (pinfunction "1_1") (pintype "passive"))
      (node (ref "IC1") (pin "5") (pinfunction "CT_5") (pintype "bidirectional"))
    )
    (net (code "33") (name "Net-(J2-PadA5)") (class "Default")
      (node (ref "J2") (pin "A5") (pinfunction "A5_A5") (pintype "bidirectional"))
      (node (ref "R2-USB1") (pin "2") (pinfunction "2_2") (pintype "passive"))
    )
    (net (code "34") (name "Net-(J2-PadB5)") (class "Default")
      (node (ref "J2") (pin "B5") (pinfunction "B5_B5") (pintype "bidirectional"))
      (node (ref "R2-USB") (pin "1") (pinfunction "1_1") (pintype "passive"))
    )
    (net (code "35") (name "Net-(MCP73831-PROG)") (class "Default")
      (node (ref "MCP73831") (pin "5") (pinfunction "PROG_5") (pintype "input"))
      (node (ref "R2_BAT") (pin "2") (pinfunction "2_2") (pintype "passive"))
    )
    (net (code "36") (name "Net-(MCP73831-STAT)") (class "Default")
      (node (ref "MCP73831") (pin "1") (pinfunction "STAT_1") (pintype "output"))
      (node (ref "R1_BAT") (pin "2") (pinfunction "2_2") (pintype "passive"))
    )
    (net (code "37") (name "PREVGH") (class "Default")
      (node (ref "D5") (pin "1") (pinfunction "K_1") (pintype "bidirectional"))
      (node (ref "EPD_C9") (pin "1") (pinfunction "1_1") (pintype "passive"))
      (node (ref "J1") (pin "21") (pinfunction "21_21") (pintype "bidirectional"))
    )
    (net (code "38") (name "PREVGL") (class "Default")
      (node (ref "D4") (pin "2") (pinfunction "A_2") (pintype "bidirectional"))
      (node (ref "EPD_C11") (pin "1") (pinfunction "1_1") (pintype "passive"))
      (node (ref "J1") (pin "23") (pinfunction "23_23") (pintype "bidirectional"))
    )
    (net (code "39") (name "RESE") (class "Default")
      (node (ref "J1") (pin "3") (pinfunction "3_3") (pintype "bidirectional"))
      (node (ref "Q3") (pin "2") (pinfunction "S_2") (pintype "bidirectional"))
      (node (ref "R3") (pin "2") (pinfunction "2_2") (pintype "passive"))
    )
    (net (code "40") (name "RESE'") (class "Default")
      (node (ref "R2") (pin "2") (pinfunction "2_2") (pintype "passive"))
      (node (ref "R3") (pin "1") (pinfunction "1_1") (pintype "passive"))
      (node (ref "SJ1") (pin "2") (pinfunction "2_2") (pintype "passive"))
    )
    (net (code "41") (name "RESET") (class "Default")
      (node (ref "C5") (pin "1") (pinfunction "1_1") (pintype "passive"))
      (node (ref "IC1") (pin "1") (pinfunction "VOUT_1") (pintype "bidirectional"))
      (node (ref "RESET_BUTTON") (pin "3") (pinfunction "3_3") (pintype "passive"))
      (node (ref "RESET_BUTTON") (pin "4") (pinfunction "4_4") (pintype "passive"))
      (node (ref "R_RESET") (pin "1") (pinfunction "1_1") (pintype "passive"))
      (node (ref "U2") (pin "3") (pinfunction "EN_3") (pintype "input"))
    )
    (net (code "42") (name "RTC_RST") (class "Default")
      (node (ref "U2") (pin "16") (pinfunction "IO18_16") (pintype "bidirectional"))
      (node (ref "U3") (pin "4") (pinfunction "~{RST}_4") (pintype "input"))
    )
    (net (code "43") (name "RX") (class "Default")
      (node (ref "TP2") (pin "TP") (pinfunction "TP_TP") (pintype "input"))
      (node (ref "U2") (pin "24") (pinfunction "RXD0/GPIO17_24") (pintype "bidirectional"))
    )
    (net (code "44") (name "SCK") (class "Default")
      (node (ref "D10") (pin "2") (pinfunction "2_2") (pintype "passive"))
      (node (ref "J1") (pin "13") (pinfunction "13_13") (pintype "bidirectional"))
      (node (ref "J10") (pin "P5") (pinfunction "CLK_P5") (pintype "bidirectional"))
      (node (ref "R6") (pin "1") (pinfunction "1_1") (pintype "passive"))
      (node (ref "TP8") (pin "TP") (pinfunction "TP_TP") (pintype "input"))
      (node (ref "U1") (pin "6") (pinfunction "CLK_6") (pintype "input"))
      (node (ref "U2") (pin "6") (pinfunction "IO6_6") (pintype "bidirectional"))
    )
    (net (code "45") (name "SCL") (class "Default")
      (node (ref "J3") (pin "4") (pinfunction "4_4") (pintype "passive"))
      (node (ref "R2-PINH") (pin "1") (pinfunction "1_1") (pintype "passive"))
      (node (ref "SENSOR2") (pin "4") (pinfunction "SCK_4") (pintype "input"))
      (node (ref "U2") (pin "20") (pinfunction "IO22_20") (pintype "bidirectional"))
      (node (ref "U3") (pin "16") (pinfunction "SCL_16") (pintype "input"))
      (node (ref "U4") (pin "7") (pinfunction "SCL_7") (pintype "input"))
    )
    (net (code "46") (name "SDA") (class "Default")
      (node (ref "J3") (pin "3") (pinfunction "3_3") (pintype "passive"))
      (node (ref "R1-PINH") (pin "1") (pinfunction "1_1") (pintype "passive"))
      (node (ref "SENSOR2") (pin "3") (pinfunction "SDI_3") (pintype "bidirectional"))
      (node (ref "U2") (pin "19") (pinfunction "IO21_19") (pintype "bidirectional"))
      (node (ref "U3") (pin "15") (pinfunction "SDA_15") (pintype "bidirectional"))
      (node (ref "U4") (pin "8") (pinfunction "SDA_8") (pintype "bidirectional"))
    )
    (net (code "47") (name "SRC") (class "Default")
      (node (ref "C4") (pin "2") (pinfunction "2_2") (pintype "passive"))
      (node (ref "D5") (pin "2") (pinfunction "A_2") (pintype "bidirectional"))
      (node (ref "L1") (pin "1") (pinfunction "1_1") (pintype "passive"))
      (node (ref "Q3") (pin "3") (pinfunction "D_3") (pintype "bidirectional"))
    )
    (net (code "48") (name "SS_SD") (class "Default")
      (node (ref "D8") (pin "2") (pinfunction "2_2") (pintype "passive"))
      (node (ref "J10") (pin "P2") (pinfunction "CD/DAT3_P2") (pintype "bidirectional"))
      (node (ref "R10") (pin "1") (pinfunction "1_1") (pintype "passive"))
      (node (ref "U2") (pin "4") (pinfunction "IO4_4") (pintype "bidirectional"))
    )
    (net (code "49") (name "TX") (class "Default")
      (node (ref "TP1") (pin "TP") (pinfunction "TP_TP") (pintype "input"))
      (node (ref "U2") (pin "25") (pinfunction "TXD0/GPIO16_25") (pintype "bidirectional"))
    )
    (net (code "50") (name "USB_D+") (class "Default")
      (node (ref "D1") (pin "1") (pinfunction "I/O1_1_1") (pintype "bidirectional"))
      (node (ref "U2") (pin "14") (pinfunction "IO13_14") (pintype "bidirectional"))
    )
    (net (code "51") (name "USB_D-") (class "Default")
      (node (ref "D1") (pin "3") (pinfunction "I/O2_1_3") (pintype "bidirectional"))
      (node (ref "U2") (pin "13") (pinfunction "IO12_13") (pintype "bidirectional"))
    )
    (net (code "52") (name "VBAT") (class "Default")
      (node (ref "C2_BAT") (pin "1") (pinfunction "1_1") (pintype "passive"))
      (node (ref "MCP73831") (pin "3") (pinfunction "VBAT_3") (pintype "power_in"))
      (node (ref "Q1") (pin "3") (pinfunction "D_3") (pintype "bidirectional"))
      (node (ref "TP3") (pin "TP") (pinfunction "TP_TP") (pintype "input"))
      (node (ref "U4") (pin "2") (pinfunction "CELL_2") (pintype "power_in"))
      (node (ref "U4") (pin "3") (pinfunction "VDD_3") (pintype "power_in"))
    )
    (net (code "53") (name "VBUS") (class "Default")
      (node (ref "C1_BAT") (pin "1") (pinfunction "1_1") (pintype "passive"))
      (node (ref "C4_USB") (pin "1") (pinfunction "1_1") (pintype "passive"))
      (node (ref "C5_USB") (pin "1") (pinfunction "1_1") (pintype "passive"))
      (node (ref "CHG_LED") (pin "A") (pinfunction "A_A") (pintype "passive"))
      (node (ref "D1") (pin "5") (pinfunction "VBUS_5") (pintype "bidirectional"))
      (node (ref "D2") (pin "2") (pinfunction "ANODE_2") (pintype "bidirectional"))
      (node (ref "MCP73831") (pin "4") (pinfunction "VIN_4") (pintype "power_in"))
      (node (ref "PFMF.050.1") (pin "2") (pinfunction "2_2") (pintype "passive"))
      (node (ref "Q1") (pin "1") (pinfunction "G_1") (pintype "bidirectional"))
      (node (ref "R1_PWRUSB") (pin "2") (pinfunction "2_2") (pintype "passive"))
      (node (ref "TP14") (pin "TP") (pinfunction "TP_TP") (pintype "input"))
    )
    (net (code "54") (name "VRTC") (class "Default")
      (node (ref "C10_SUPERCAP") (pin "2") (pinfunction "2_2") (pintype "passive"))
      (node (ref "C8") (pin "1") (pinfunction "1_1") (pintype "passive"))
      (node (ref "R_CAPACITOR") (pin "2") (pinfunction "2_2") (pintype "passive"))
      (node (ref "U3") (pin "14") (pinfunction "VBAT_14") (pintype "power_in"))
    )
    (net (code "55") (name "VUSB") (class "Default")
      (node (ref "J2") (pin "A4") (pinfunction "A4_A4") (pintype "bidirectional"))
      (node (ref "J2") (pin "A9") (pinfunction "A9_A9") (pintype "bidirectional"))
      (node (ref "J2") (pin "B4") (pinfunction "B4_B4") (pintype "bidirectional"))
      (node (ref "J2") (pin "B9") (pinfunction "B9_B9") (pintype "bidirectional"))
      (node (ref "PFMF.050.1") (pin "1") (pinfunction "1_1") (pintype "passive"))
    )
    (net (code "56") (name "unconnected-(IC1-NC-Pad4)") (class "Default")
      (node (ref "IC1") (pin "4") (pinfunction "NC_4") (pintype "no_connect"))
    )
    (net (code "57") (name "unconnected-(IC4-NC-Pad4)") (class "Default")
      (node (ref "IC4") (pin "4") (pinfunction "NC_4") (pintype "no_connect"))
    )
    (net (code "58") (name "unconnected-(J1-Pad1)") (class "Default")
      (node (ref "J1") (pin "1") (pinfunction "1_1") (pintype "bidirectional"))
    )
    (net (code "59") (name "unconnected-(J1-Pad6)") (class "Default")
      (node (ref "J1") (pin "6") (pinfunction "6_6") (pintype "bidirectional"))
    )
    (net (code "60") (name "unconnected-(J1-Pad7)") (class "Default")
      (node (ref "J1") (pin "7") (pinfunction "7_7") (pintype "bidirectional"))
    )
    (net (code "61") (name "unconnected-(J2-PadA8)") (class "Default")
      (node (ref "J2") (pin "A8") (pinfunction "A8_A8") (pintype "bidirectional"))
    )
    (net (code "62") (name "unconnected-(J2-PadB8)") (class "Default")
      (node (ref "J2") (pin "B8") (pinfunction "B8_B8") (pintype "bidirectional"))
    )
    (net (code "63") (name "unconnected-(J10-DAT1-PadP8)") (class "Default")
      (node (ref "J10") (pin "P8") (pinfunction "DAT1_P8") (pintype "bidirectional"))
    )
    (net (code "64") (name "unconnected-(J10-DAT2-PadP1)") (class "Default")
      (node (ref "J10") (pin "P1") (pinfunction "DAT2_P1") (pintype "bidirectional"))
    )
    (net (code "65") (name "unconnected-(J10-DETECTION_1-PadS1)") (class "Default")
      (node (ref "J10") (pin "S1") (pinfunction "DETECTION_1_S1") (pintype "bidirectional"))
    )
    (net (code "66") (name "unconnected-(J10-DETECTION_2-PadS2)") (class "Default")
      (node (ref "J10") (pin "S2") (pinfunction "DETECTION_2_S2") (pintype "bidirectional"))
    )
    (net (code "67") (name "unconnected-(U2-NC-Pad22)") (class "Default")
      (node (ref "U2") (pin "22") (pinfunction "NC_22") (pintype "no_connect"))
    )
    (net (code "68") (name "unconnected-(U4-~{ALERT}-Pad5)") (class "Default")
      (node (ref "U4") (pin "5") (pinfunction "~{ALERT}_5") (pintype "output"))
    )
  )
)
